# Shutdown_ckt.net
KiCad netlist of a schematic drawn in Altium Designer
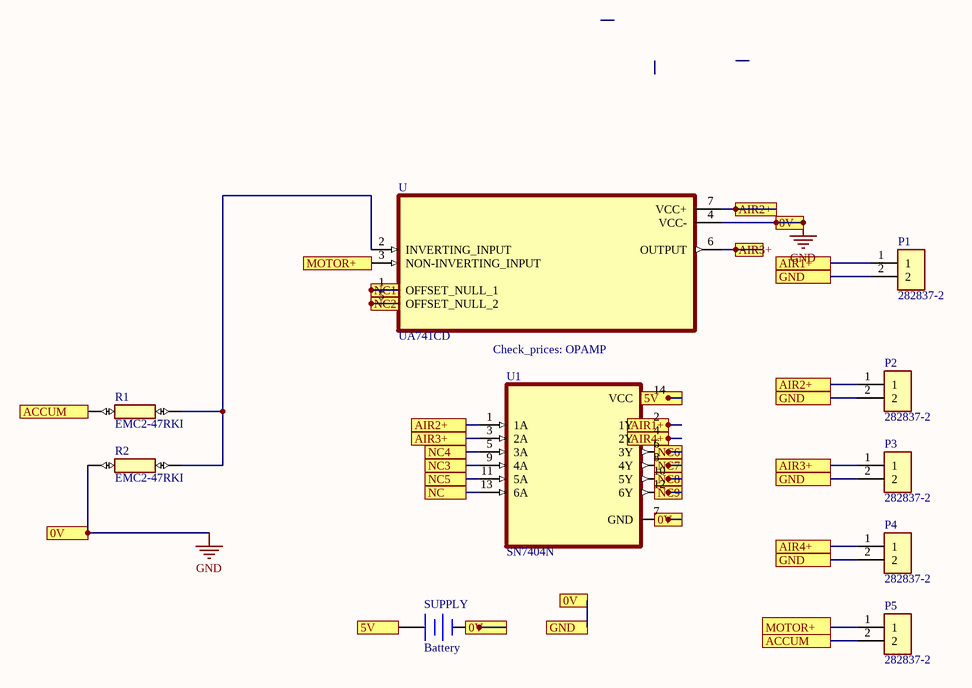
[diagram p0: Shutdown_ckt.SchDoc]

(export (version "E")
  (design (tool "Eeschema 10.0.6"))
  (components
    (comp (ref "P1")
      (value "282837-2")
      (footprint "TE_282837-2")
      (fields (field (name "MF") "TE Connectivity"))
      (libsource (lib "282837-2") (part "282837-2"))
    )
    (comp (ref "P2")
      (value "282837-2")
      (footprint "TE_282837-2")
      (fields (field (name "MF") "TE Connectivity"))
      (libsource (lib "282837-2") (part "282837-2"))
    )
    (comp (ref "P3")
      (value "282837-2")
      (footprint "TE_282837-2")
      (fields (field (name "MF") "TE Connectivity"))
      (libsource (lib "282837-2") (part "282837-2"))
    )
    (comp (ref "P4")
      (value "282837-2")
      (footprint "TE_282837-2")
      (fields (field (name "MF") "TE Connectivity"))
      (libsource (lib "282837-2") (part "282837-2"))
    )
    (comp (ref "P5")
      (value "282837-2")
      (footprint "TE_282837-2")
      (fields (field (name "MF") "TE Connectivity"))
      (libsource (lib "282837-2") (part "282837-2"))
    )
    (comp (ref "R1")
      (value "EMC2-47RKI")
      (footprint "RESAD2600W80L1000D400")
      (description "RES 47 OHM 2W 10% AXIAL")
      (fields (field (name "MF") "TT Electronics/Welwyn"))
      (libsource (lib "EMC2-47RKI") (part "EMC2-47RKI"))
    )
    (comp (ref "R2")
      (value "EMC2-47RKI")
      (footprint "RESAD2600W80L1000D400")
      (description "RES 47 OHM 2W 10% AXIAL")
      (fields (field (name "MF") "TT Electronics/Welwyn"))
      (libsource (lib "EMC2-47RKI") (part "EMC2-47RKI"))
    )
    (comp (ref "SUPPLY")
      (value "Battery")
      (footprint "BAT-2")
      (description "Multicell Battery")
      (fields (field (name "PUBLISHER") "Altium Limited"))
      (libsource (lib "Miscellaneous Devices") (part "Battery"))
    )
    (comp (ref "U")
      (value "UA741CD")
      (footprint "SOIC127P599X175-8N")
      (description "General-Purpose Operational Amplifier 8-SOIC 0 to 70")
      (fields (field (name "MF") "Texas Instruments") (field (name "CHECK_PRICES") "OPAMP"))
      (libsource (lib "UA741CD") (part "UA741CD"))
    )
    (comp (ref "U1")
      (value "SN7404N")
      (footprint "DIP794W45P254L1969H508Q14")
      (description "6-ch, 4.75-V to 5.25-V bipolar inverters")
      (fields (field (name "MF") "Texas Instruments"))
      (libsource (lib "SN7404N") (part "SN7404N"))
    )
  )
  (nets
    (net (code "1") (name "/5V") (class "Default")
      (node (ref "SUPPLY") (pin "1") (pinfunction "+_1") (pintype "passive"))
      (node (ref "U1") (pin "14") (pinfunction "VCC_14") (pintype "power_in"))
    )
    (net (code "2") (name "/ACCUM") (class "Default")
      (node (ref "P5") (pin "2") (pinfunction "2_2") (pintype "passive"))
      (node (ref "R1") (pin "1") (pinfunction "1_1") (pintype "bidirectional"))
    )
    (net (code "3") (name "/AIR1+") (class "Default")
      (node (ref "P1") (pin "1") (pinfunction "1_1") (pintype "passive"))
      (node (ref "U1") (pin "2") (pinfunction "1Y_2") (pintype "output"))
    )
    (net (code "4") (name "/AIR2+") (class "Default")
      (node (ref "P2") (pin "1") (pinfunction "1_1") (pintype "passive"))
      (node (ref "U") (pin "7") (pinfunction "VCC+_7") (pintype "power_in"))
      (node (ref "U1") (pin "1") (pinfunction "1A_1") (pintype "input"))
    )
    (net (code "5") (name "/AIR3+") (class "Default")
      (node (ref "P3") (pin "1") (pinfunction "1_1") (pintype "passive"))
      (node (ref "U") (pin "6") (pinfunction "OUTPUT_6") (pintype "output"))
      (node (ref "U1") (pin "3") (pinfunction "2A_3") (pintype "input"))
    )
    (net (code "6") (name "/AIR4+") (class "Default")
      (node (ref "P4") (pin "1") (pinfunction "1_1") (pintype "passive"))
      (node (ref "U1") (pin "4") (pinfunction "2Y_4") (pintype "output"))
    )
    (net (code "7") (name "/MOTOR+") (class "Default")
      (node (ref "P5") (pin "1") (pinfunction "1_1") (pintype "passive"))
      (node (ref "U") (pin "3") (pinfunction "NON-INVERTING_INPUT_3") (pintype "input"))
    )
    (net (code "8") (name "/NC") (class "Default")
      (node (ref "U1") (pin "13") (pinfunction "6A_13") (pintype "input"))
    )
    (net (code "9") (name "/NC1") (class "Default")
      (node (ref "U") (pin "1") (pinfunction "OFFSET_NULL_1_1") (pintype "bidirectional"))
    )
    (net (code "10") (name "/NC2") (class "Default")
      (node (ref "U") (pin "5") (pinfunction "OFFSET_NULL_2_5") (pintype "bidirectional"))
    )
    (net (code "11") (name "/NC3") (class "Default")
      (node (ref "U1") (pin "9") (pinfunction "4A_9") (pintype "input"))
    )
    (net (code "12") (name "/NC4") (class "Default")
      (node (ref "U1") (pin "5") (pinfunction "3A_5") (pintype "input"))
    )
    (net (code "13") (name "/NC5") (class "Default")
      (node (ref "U1") (pin "11") (pinfunction "5A_11") (pintype "input"))
    )
    (net (code "14") (name "/NC6") (class "Default")
      (node (ref "U1") (pin "6") (pinfunction "3Y_6") (pintype "output"))
    )
    (net (code "15") (name "/NC7") (class "Default")
      (node (ref "U1") (pin "8") (pinfunction "4Y_8") (pintype "output"))
    )
    (net (code "16") (name "/NC8") (class "Default")
      (node (ref "U1") (pin "10") (pinfunction "5Y_10") (pintype "output"))
    )
    (net (code "17") (name "/NC9") (class "Default")
      (node (ref "U1") (pin "12") (pinfunction "6Y_12") (pintype "output"))
    )
    (net (code "18") (name "GND") (class "Default")
      (node (ref "P1") (pin "2") (pinfunction "2_2") (pintype "passive"))
      (node (ref "P2") (pin "2") (pinfunction "2_2") (pintype "passive"))
      (node (ref "P3") (pin "2") (pinfunction "2_2") (pintype "passive"))
      (node (ref "P4") (pin "2") (pinfunction "2_2") (pintype "passive"))
      (node (ref "R2") (pin "1") (pinfunction "1_1") (pintype "bidirectional"))
      (node (ref "SUPPLY") (pin "2") (pinfunction "-_2") (pintype "passive"))
      (node (ref "U") (pin "4") (pinfunction "VCC-_4") (pintype "power_in"))
      (node (ref "U1") (pin "7") (pinfunction "GND_7") (pintype "power_in"))
    )
    (net (code "19") (name "Net-(U-INVERTING_INPUT)") (class "Default")
      (node (ref "R1") (pin "2") (pinfunction "2_2") (pintype "bidirectional"))
      (node (ref "R2") (pin "2") (pinfunction "2_2") (pintype "bidirectional"))
      (node (ref "U") (pin "2") (pinfunction "INVERTING_INPUT_2") (pintype "input"))
    )
  )
)
